# Sheet1.net
KiCad netlist of a schematic drawn in Altium Designer
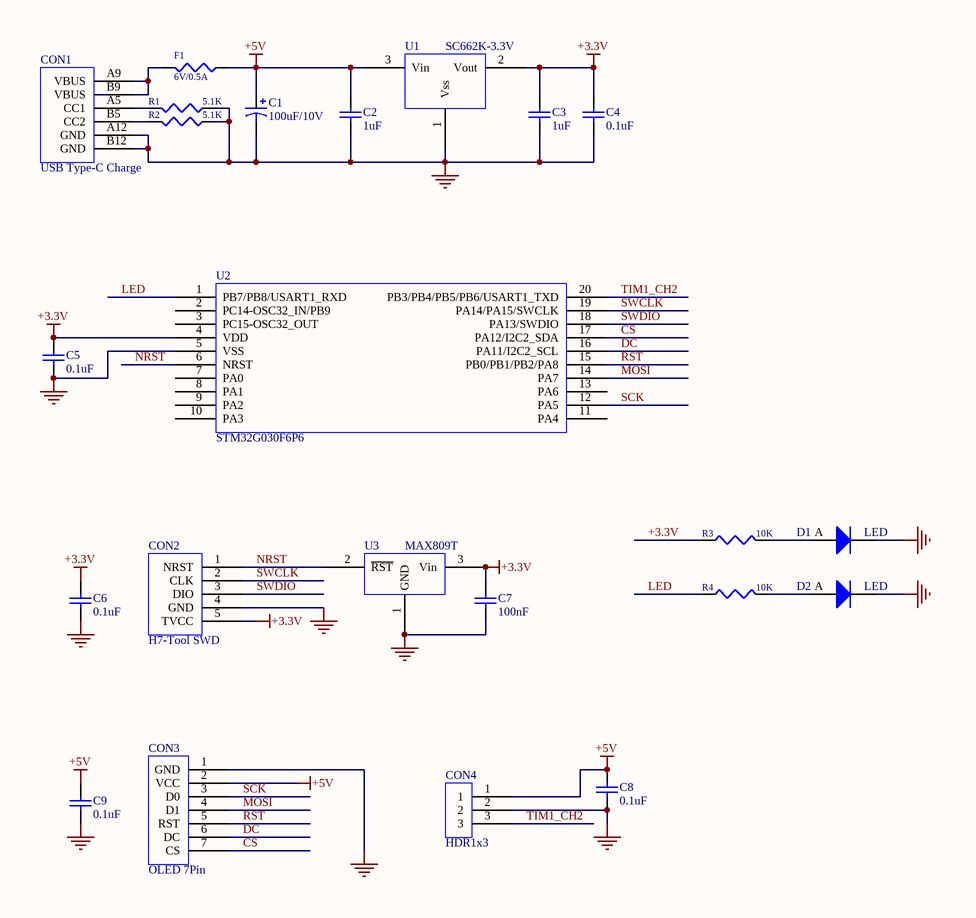
[diagram p0: Sheet1.SchDoc]

(export (version "E")
  (design (tool "Eeschema 10.0.6"))
  (components
    (comp (ref "C1")
      (value "100uF/10V")
      (footprint "CM C(5*5.4)")
      (description "Polarized Capacitor (Radial)")
      (fields (field (name "Comment") "Cap Pol1") (field (name "PUBLISHER") "Altium Limited"))
      (libsource (lib "Miscellaneous Devices") (part "Cap Pol1"))
    )
    (comp (ref "C2")
      (value "1uF")
      (footprint "0603_C")
      (description "贴片电容")
      (libsource (lib "Miscellaneous Devices LC") (part "0603 100nF (104) 10% 50V"))
    )
    (comp (ref "C3")
      (value "1uF")
      (footprint "0603_C")
      (description "贴片电容")
      (libsource (lib "Miscellaneous Devices LC") (part "0603 100nF (104) 10% 50V"))
    )
    (comp (ref "C4")
      (value "0.1uF")
      (footprint "0603_C")
      (description "贴片电容")
      (libsource (lib "Miscellaneous Devices LC") (part "0603 100nF (104) 10% 50V"))
    )
    (comp (ref "C5")
      (value "0.1uF")
      (footprint "0603_C")
      (description "贴片电容")
      (libsource (lib "Miscellaneous Devices LC") (part "0603 100nF (104) 10% 50V"))
    )
    (comp (ref "C6")
      (value "0.1uF")
      (footprint "0603_C")
      (description "贴片电容")
      (libsource (lib "Miscellaneous Devices LC") (part "0603 100nF (104) 10% 50V"))
    )
    (comp (ref "C7")
      (value "100nF")
      (footprint "0603_C")
      (description "贴片电容")
      (libsource (lib "Miscellaneous Devices LC") (part "0603 100nF (104) 10% 50V"))
    )
    (comp (ref "C8")
      (value "0.1uF")
      (footprint "0603_C")
      (description "贴片电容")
      (libsource (lib "Miscellaneous Devices LC") (part "0603 100nF (104) 10% 50V"))
    )
    (comp (ref "C9")
      (value "0.1uF")
      (footprint "0603_C")
      (description "贴片电容")
      (libsource (lib "Miscellaneous Devices LC") (part "0603 100nF (104) 10% 50V"))
    )
    (comp (ref "CON1")
      (value "USB Type-C Charge")
      (footprint "Type-C_4charge")
      (libsource (lib "原理图库") (part "USB Type-C Charge"))
    )
    (comp (ref "CON2")
      (value "H7-Tool SWD")
      (footprint "hdr1x5")
      (libsource (lib "原理图库") (part "H7-Tool SWD"))
    )
    (comp (ref "CON3")
      (value "OLED 7Pin")
      (footprint "0.96 OLED SPI")
      (libsource (lib "原理图库") (part "OLED 7Pin"))
    )
    (comp (ref "CON4") (value "HDR1x3") (footprint "XH2.54-LI-3P") (libsource (lib "原理图库") (part "HDR1x3")))
    (comp (ref "D1")
      (value "LED")
      (footprint "0603_LED_S1")
      (description "二极管")
      (libsource (lib "Schlib1") (part "Diode"))
    )
    (comp (ref "D2")
      (value "LED")
      (footprint "0603_LED_S1")
      (description "二极管")
      (libsource (lib "Schlib1") (part "Diode"))
    )
    (comp (ref "F1")
      (value "6V/0.5A")
      (footprint "0603_L")
      (description "Resistor")
      (libsource (lib "*") (part "RES"))
    )
    (comp (ref "R1")
      (value "5.1K")
      (footprint "0603_R")
      (description "Resistor")
      (libsource (lib "*") (part "RES"))
    )
    (comp (ref "R2")
      (value "5.1K")
      (footprint "0603_R")
      (description "Resistor")
      (libsource (lib "*") (part "RES"))
    )
    (comp (ref "R3")
      (value "10K")
      (footprint "0603_R")
      (description "Resistor")
      (libsource (lib "*") (part "RES"))
    )
    (comp (ref "R4")
      (value "10K")
      (footprint "0603_R")
      (description "Resistor")
      (libsource (lib "*") (part "RES"))
    )
    (comp (ref "U1")
      (value "SC662K-3.3V")
      (footprint "SOT-23(SOT-23-3)")
      (description "Vinmax=6v;Ioutmax=250mA; 1.8V LDO")
      (libsource (lib "原理图库") (part "SC662K-3.3V"))
    )
    (comp (ref "U2")
      (value "STM32G030F6P6")
      (footprint "TSSOP-20")
      (libsource (lib "原理图库") (part "STM32G030F6P6"))
    )
    (comp (ref "U3")
      (value "MAX809T")
      (footprint "SOT-23(SOT-23-3)")
      (description "3.08v")
      (libsource (lib "Schlib1") (part "MAX809T"))
    )
  )
  (nets
    (net (code "1") (name "+3.3V") (class "Default")
      (node (ref "C3") (pin "2") (pinfunction "2_2") (pintype "passive"))
      (node (ref "C4") (pin "2") (pinfunction "2_2") (pintype "passive"))
      (node (ref "C5") (pin "2") (pinfunction "2_2") (pintype "passive"))
      (node (ref "C6") (pin "2") (pinfunction "2_2") (pintype "passive"))
      (node (ref "C7") (pin "1") (pinfunction "1_1") (pintype "passive"))
      (node (ref "CON2") (pin "5") (pinfunction "TVCC_5") (pintype "passive"))
      (node (ref "R3") (pin "2") (pinfunction "BOT_2") (pintype "passive"))
      (node (ref "U1") (pin "2") (pinfunction "Vout_2") (pintype "passive"))
      (node (ref "U2") (pin "4") (pinfunction "VDD_4") (pintype "passive"))
      (node (ref "U3") (pin "3") (pinfunction "Vin_3") (pintype "passive"))
    )
    (net (code "2") (name "+5V") (class "Default")
      (node (ref "C1") (pin "1") (pinfunction "1_1") (pintype "passive"))
      (node (ref "C2") (pin "2") (pinfunction "2_2") (pintype "passive"))
      (node (ref "C8") (pin "2") (pinfunction "2_2") (pintype "passive"))
      (node (ref "C9") (pin "2") (pinfunction "2_2") (pintype "passive"))
      (node (ref "CON3") (pin "2") (pinfunction "VCC_2") (pintype "passive"))
      (node (ref "CON4") (pin "1") (pinfunction "1_1") (pintype "passive"))
      (node (ref "F1") (pin "2") (pinfunction "BOT_2") (pintype "passive"))
      (node (ref "U1") (pin "3") (pinfunction "Vin_3") (pintype "passive"))
    )
    (net (code "3") (name "/CS") (class "Default")
      (node (ref "CON3") (pin "7") (pinfunction "CS_7") (pintype "passive"))
      (node (ref "U2") (pin "17") (pinfunction "PA12/I2C2_SDA_17") (pintype "passive"))
    )
    (net (code "4") (name "/DC") (class "Default")
      (node (ref "CON3") (pin "6") (pinfunction "DC_6") (pintype "passive"))
      (node (ref "U2") (pin "16") (pinfunction "PA11/I2C2_SCL_16") (pintype "passive"))
    )
    (net (code "5") (name "/LED") (class "Default")
      (node (ref "R4") (pin "2") (pinfunction "BOT_2") (pintype "passive"))
      (node (ref "U2") (pin "1") (pinfunction "PB7/PB8/USART1_RXD_1") (pintype "passive"))
    )
    (net (code "6") (name "/MOSI") (class "Default")
      (node (ref "CON3") (pin "4") (pinfunction "D1_4") (pintype "passive"))
      (node (ref "U2") (pin "14") (pinfunction "PA7_14") (pintype "passive"))
    )
    (net (code "7") (name "/NRST") (class "Default")
      (node (ref "CON2") (pin "1") (pinfunction "NRST_1") (pintype "passive"))
      (node (ref "U2") (pin "6") (pinfunction "NRST_6") (pintype "passive"))
      (node (ref "U3") (pin "2") (pinfunction "~{RST}_2") (pintype "passive"))
    )
    (net (code "8") (name "/RST") (class "Default")
      (node (ref "CON3") (pin "5") (pinfunction "RST_5") (pintype "passive"))
      (node (ref "U2") (pin "15") (pinfunction "PB0/PB1/PB2/PA8_15") (pintype "passive"))
    )
    (net (code "9") (name "/SCK") (class "Default")
      (node (ref "CON3") (pin "3") (pinfunction "D0_3") (pintype "passive"))
      (node (ref "U2") (pin "12") (pinfunction "PA5_12") (pintype "passive"))
    )
    (net (code "10") (name "/SWCLK") (class "Default")
      (node (ref "CON2") (pin "2") (pinfunction "CLK_2") (pintype "passive"))
      (node (ref "U2") (pin "19") (pinfunction "PA14/PA15/SWCLK_19") (pintype "passive"))
    )
    (net (code "11") (name "/SWDIO") (class "Default")
      (node (ref "CON2") (pin "3") (pinfunction "DIO_3") (pintype "passive"))
      (node (ref "U2") (pin "18") (pinfunction "PA13/SWDIO_18") (pintype "passive"))
    )
    (net (code "12") (name "/TIM1_CH2") (class "Default")
      (node (ref "CON4") (pin "3") (pinfunction "3_3") (pintype "passive"))
      (node (ref "U2") (pin "20") (pinfunction "PB3/PB4/PB5/PB6/USART1_TXD_20") (pintype "passive"))
    )
    (net (code "13") (name "GND") (class "Default")
      (node (ref "C1") (pin "2") (pinfunction "2_2") (pintype "passive"))
      (node (ref "C2") (pin "1") (pinfunction "1_1") (pintype "passive"))
      (node (ref "C3") (pin "1") (pinfunction "1_1") (pintype "passive"))
      (node (ref "C4") (pin "1") (pinfunction "1_1") (pintype "passive"))
      (node (ref "C5") (pin "1") (pinfunction "1_1") (pintype "passive"))
      (node (ref "C6") (pin "1") (pinfunction "1_1") (pintype "passive"))
      (node (ref "C7") (pin "2") (pinfunction "2_2") (pintype "passive"))
      (node (ref "C8") (pin "1") (pinfunction "1_1") (pintype "passive"))
      (node (ref "C9") (pin "1") (pinfunction "1_1") (pintype "passive"))
      (node (ref "CON1") (pin "A12") (pinfunction "GND_A12") (pintype "passive"))
      (node (ref "CON1") (pin "B12") (pinfunction "GND_B12") (pintype "passive"))
      (node (ref "CON2") (pin "4") (pinfunction "GND_4") (pintype "passive"))
      (node (ref "CON3") (pin "1") (pinfunction "GND_1") (pintype "passive"))
      (node (ref "CON4") (pin "2") (pinfunction "2_2") (pintype "passive"))
      (node (ref "D1") (pin "K") (pinfunction "K_K") (pintype "passive"))
      (node (ref "D2") (pin "K") (pinfunction "K_K") (pintype "passive"))
      (node (ref "R1") (pin "2") (pinfunction "BOT_2") (pintype "passive"))
      (node (ref "R2") (pin "2") (pinfunction "BOT_2") (pintype "passive"))
      (node (ref "U1") (pin "1") (pinfunction "Vss_1") (pintype "passive"))
      (node (ref "U2") (pin "5") (pinfunction "VSS_5") (pintype "passive"))
      (node (ref "U3") (pin "1") (pinfunction "GND_1") (pintype "passive"))
    )
    (net (code "14") (name "Net-(CON1-CC1)") (class "Default")
      (node (ref "CON1") (pin "A5") (pinfunction "CC1_A5") (pintype "passive"))
      (node (ref "R1") (pin "1") (pinfunction "TOP_1") (pintype "passive"))
    )
    (net (code "15") (name "Net-(CON1-CC2)") (class "Default")
      (node (ref "CON1") (pin "B5") (pinfunction "CC2_B5") (pintype "passive"))
      (node (ref "R2") (pin "1") (pinfunction "TOP_1") (pintype "passive"))
    )
    (net (code "16") (name "Net-(F1-TOP)") (class "Default")
      (node (ref "CON1") (pin "A9") (pinfunction "VBUS_A9") (pintype "passive"))
      (node (ref "CON1") (pin "B9") (pinfunction "VBUS_B9") (pintype "passive"))
      (node (ref "F1") (pin "1") (pinfunction "TOP_1") (pintype "passive"))
    )
    (net (code "17") (name "Net-(R3-TOP)") (class "Default")
      (node (ref "D1") (pin "A") (pinfunction "A_A") (pintype "passive"))
      (node (ref "R3") (pin "1") (pinfunction "TOP_1") (pintype "passive"))
    )
    (net (code "18") (name "Net-(R4-TOP)") (class "Default")
      (node (ref "D2") (pin "A") (pinfunction "A_A") (pintype "passive"))
      (node (ref "R4") (pin "1") (pinfunction "TOP_1") (pintype "passive"))
    )
    (net (code "19") (name "unconnected-(U2-PA0-Pad7)") (class "Default")
      (node (ref "U2") (pin "7") (pinfunction "PA0_7") (pintype "passive"))
    )
    (net (code "20") (name "unconnected-(U2-PA1-Pad8)") (class "Default")
      (node (ref "U2") (pin "8") (pinfunction "PA1_8") (pintype "passive"))
    )
    (net (code "21") (name "unconnected-(U2-PA2-Pad9)") (class "Default")
      (node (ref "U2") (pin "9") (pinfunction "PA2_9") (pintype "passive"))
    )
    (net (code "22") (name "unconnected-(U2-PA3-Pad10)") (class "Default")
      (node (ref "U2") (pin "10") (pinfunction "PA3_10") (pintype "passive"))
    )
    (net (code "23") (name "unconnected-(U2-PA4-Pad11)") (class "Default")
      (node (ref "U2") (pin "11") (pinfunction "PA4_11") (pintype "passive"))
    )
    (net (code "24") (name "unconnected-(U2-PA6-Pad13)") (class "Default")
      (node (ref "U2") (pin "13") (pinfunction "PA6_13") (pintype "passive"))
    )
    (net (code "25") (name "unconnected-(U2-PC14-OSC32_IN{slash}PB9-Pad2)") (class "Default")
      (node (ref "U2") (pin "2") (pinfunction "PC14-OSC32_IN/PB9_2") (pintype "passive"))
    )
    (net (code "26") (name "unconnected-(U2-PC15-OSC32_OUT-Pad3)") (class "Default")
      (node (ref "U2") (pin "3") (pinfunction "PC15-OSC32_OUT_3") (pintype "passive"))
    )
  )
)
